# MIDI_Schematic.net
KiCad netlist of a schematic drawn in Altium Designer
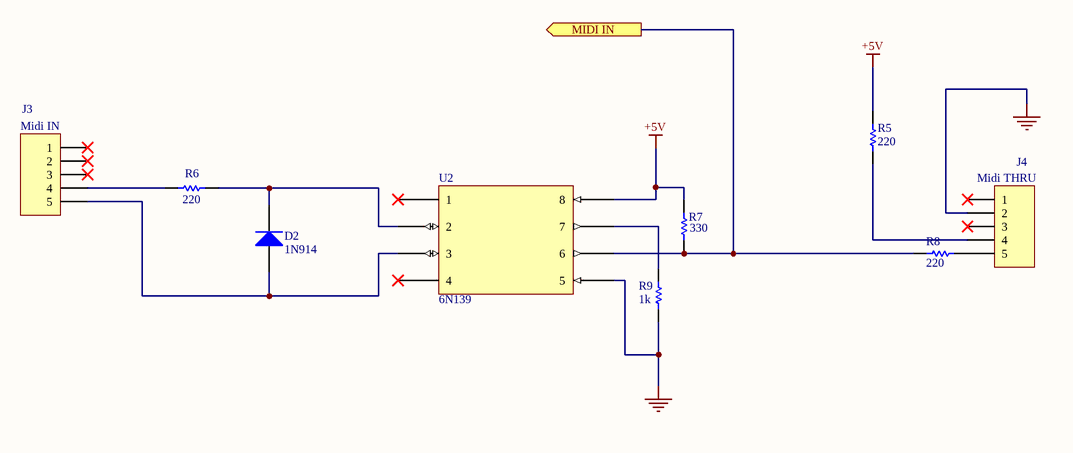
[diagram p0: MIDI.Schematic.SchDoc]

(export (version "E")
  (design (tool "Eeschema 10.0.6"))
  (components
    (comp (ref "D2")
      (value "1N914")
      (footprint "1N914")
      (description "Default Diode")
      (fields (field (name "PUBLISHER") "Altium Limited"))
      (libsource (lib "Miscellaneous Devices") (part "Diode"))
    )
    (comp (ref "J3")
      (value "Midi IN")
      (footprint "SOCKET MIDI")
      (description "DIN 5 Pins")
      (fields (field (name "PUBLISHER") "Altium Limited"))
      (libsource (lib "Miscellaneous Connectors") (part "Header 5"))
    )
    (comp (ref "J4")
      (value "Midi THRU")
      (footprint "SOCKET MIDI")
      (description "DIN 5 Pins")
      (fields (field (name "PUBLISHER") "Altium Limited"))
      (libsource (lib "") (part "Header 5_1"))
    )
    (comp (ref "R5")
      (value "220")
      (footprint "CAPC1608N")
      (description "Resistor")
      (fields (field (name "Comment") "Res1") (field (name "PUBLISHER") "Altium Limited"))
      (libsource (lib "Miscellaneous Devices") (part "Res1"))
    )
    (comp (ref "R6")
      (value "220")
      (footprint "CAPC1608N")
      (description "Resistor")
      (fields (field (name "Comment") "Res1") (field (name "PUBLISHER") "Altium Limited"))
      (libsource (lib "Miscellaneous Devices") (part "Res1"))
    )
    (comp (ref "R7")
      (value "330")
      (footprint "CAPC1608N")
      (description "Resistor")
      (fields (field (name "PUBLISHER") "Altium Limited"))
      (libsource (lib "Miscellaneous Devices") (part "Res1"))
    )
    (comp (ref "R8")
      (value "220")
      (footprint "CAPC1608N")
      (description "Resistor")
      (fields (field (name "Comment") "Res1") (field (name "PUBLISHER") "Altium Limited"))
      (libsource (lib "Miscellaneous Devices") (part "Res1"))
    )
    (comp (ref "R9")
      (value "1k")
      (footprint "CAPC1608N")
      (description "Resistor")
      (fields (field (name "PUBLISHER") "Altium Limited"))
      (libsource (lib "Miscellaneous Devices") (part "Res1"))
    )
    (comp (ref "U2")
      (value "6N139")
      (footprint "6N139")
      (libsource (lib "SynthyTwo.Components") (part "Optocoupleur"))
    )
  )
  (nets
    (net (code "1") (name "+5V") (class "Default")
      (node (ref "R5") (pin "2") (pinfunction "2_2") (pintype "passive"))
      (node (ref "R7") (pin "2") (pinfunction "2_2") (pintype "passive"))
      (node (ref "U2") (pin "8") (pinfunction "8_8") (pintype "input"))
    )
    (net (code "2") (name "/MIDI IN") (class "Default")
      (node (ref "R7") (pin "1") (pinfunction "1_1") (pintype "passive"))
      (node (ref "R8") (pin "2") (pinfunction "2_2") (pintype "passive"))
      (node (ref "U2") (pin "6") (pinfunction "6_6") (pintype "output"))
    )
    (net (code "3") (name "GND") (class "Default")
      (node (ref "J4") (pin "2") (pinfunction "2_2") (pintype "passive"))
      (node (ref "R9") (pin "1") (pinfunction "1_1") (pintype "passive"))
      (node (ref "U2") (pin "5") (pinfunction "5_5") (pintype "input"))
    )
    (net (code "4") (name "Net-(D2-A)") (class "Default")
      (node (ref "D2") (pin "1") (pinfunction "A_1") (pintype "passive"))
      (node (ref "J3") (pin "5") (pinfunction "5_5") (pintype "passive"))
      (node (ref "U2") (pin "3") (pinfunction "3_3") (pintype "bidirectional"))
    )
    (net (code "5") (name "Net-(D2-K)") (class "Default")
      (node (ref "D2") (pin "2") (pinfunction "K_2") (pintype "passive"))
      (node (ref "R6") (pin "2") (pinfunction "2_2") (pintype "passive"))
      (node (ref "U2") (pin "2") (pinfunction "2_2") (pintype "bidirectional"))
    )
    (net (code "6") (name "Net-(J3-Pad4)") (class "Default")
      (node (ref "J3") (pin "4") (pinfunction "4_4") (pintype "passive"))
      (node (ref "R6") (pin "1") (pinfunction "1_1") (pintype "passive"))
    )
    (net (code "7") (name "Net-(J4-Pad4)") (class "Default")
      (node (ref "J4") (pin "4") (pinfunction "4_4") (pintype "passive"))
      (node (ref "R5") (pin "1") (pinfunction "1_1") (pintype "passive"))
    )
    (net (code "8") (name "Net-(J4-Pad5)") (class "Default")
      (node (ref "J4") (pin "5") (pinfunction "5_5") (pintype "passive"))
      (node (ref "R8") (pin "1") (pinfunction "1_1") (pintype "passive"))
    )
    (net (code "9") (name "Net-(R9-Pad2)") (class "Default")
      (node (ref "R9") (pin "2") (pinfunction "2_2") (pintype "passive"))
      (node (ref "U2") (pin "7") (pinfunction "7_7") (pintype "output"))
    )
    (net (code "10") (name "unconnected-(J3-Pad1)") (class "Default")
      (node (ref "J3") (pin "1") (pinfunction "1_1") (pintype "passive+no_connect"))
    )
    (net (code "11") (name "unconnected-(J3-Pad2)") (class "Default")
      (node (ref "J3") (pin "2") (pinfunction "2_2") (pintype "passive+no_connect"))
    )
    (net (code "12") (name "unconnected-(J3-Pad3)") (class "Default")
      (node (ref "J3") (pin "3") (pinfunction "3_3") (pintype "passive+no_connect"))
    )
    (net (code "13") (name "unconnected-(J4-Pad1)") (class "Default")
      (node (ref "J4") (pin "1") (pinfunction "1_1") (pintype "passive+no_connect"))
    )
    (net (code "14") (name "unconnected-(J4-Pad3)") (class "Default")
      (node (ref "J4") (pin "3") (pinfunction "3_3") (pintype "passive+no_connect"))
    )
    (net (code "15") (name "unconnected-(U2-Pad1)") (class "Default")
      (node (ref "U2") (pin "1") (pinfunction "1_1") (pintype "passive+no_connect"))
    )
    (net (code "16") (name "unconnected-(U2-Pad4)") (class "Default")
      (node (ref "U2") (pin "4") (pinfunction "4_4") (pintype "passive+no_connect"))
    )
  )
)
